# Motor-Connector.net
KiCad netlist of a schematic drawn in Altium Designer
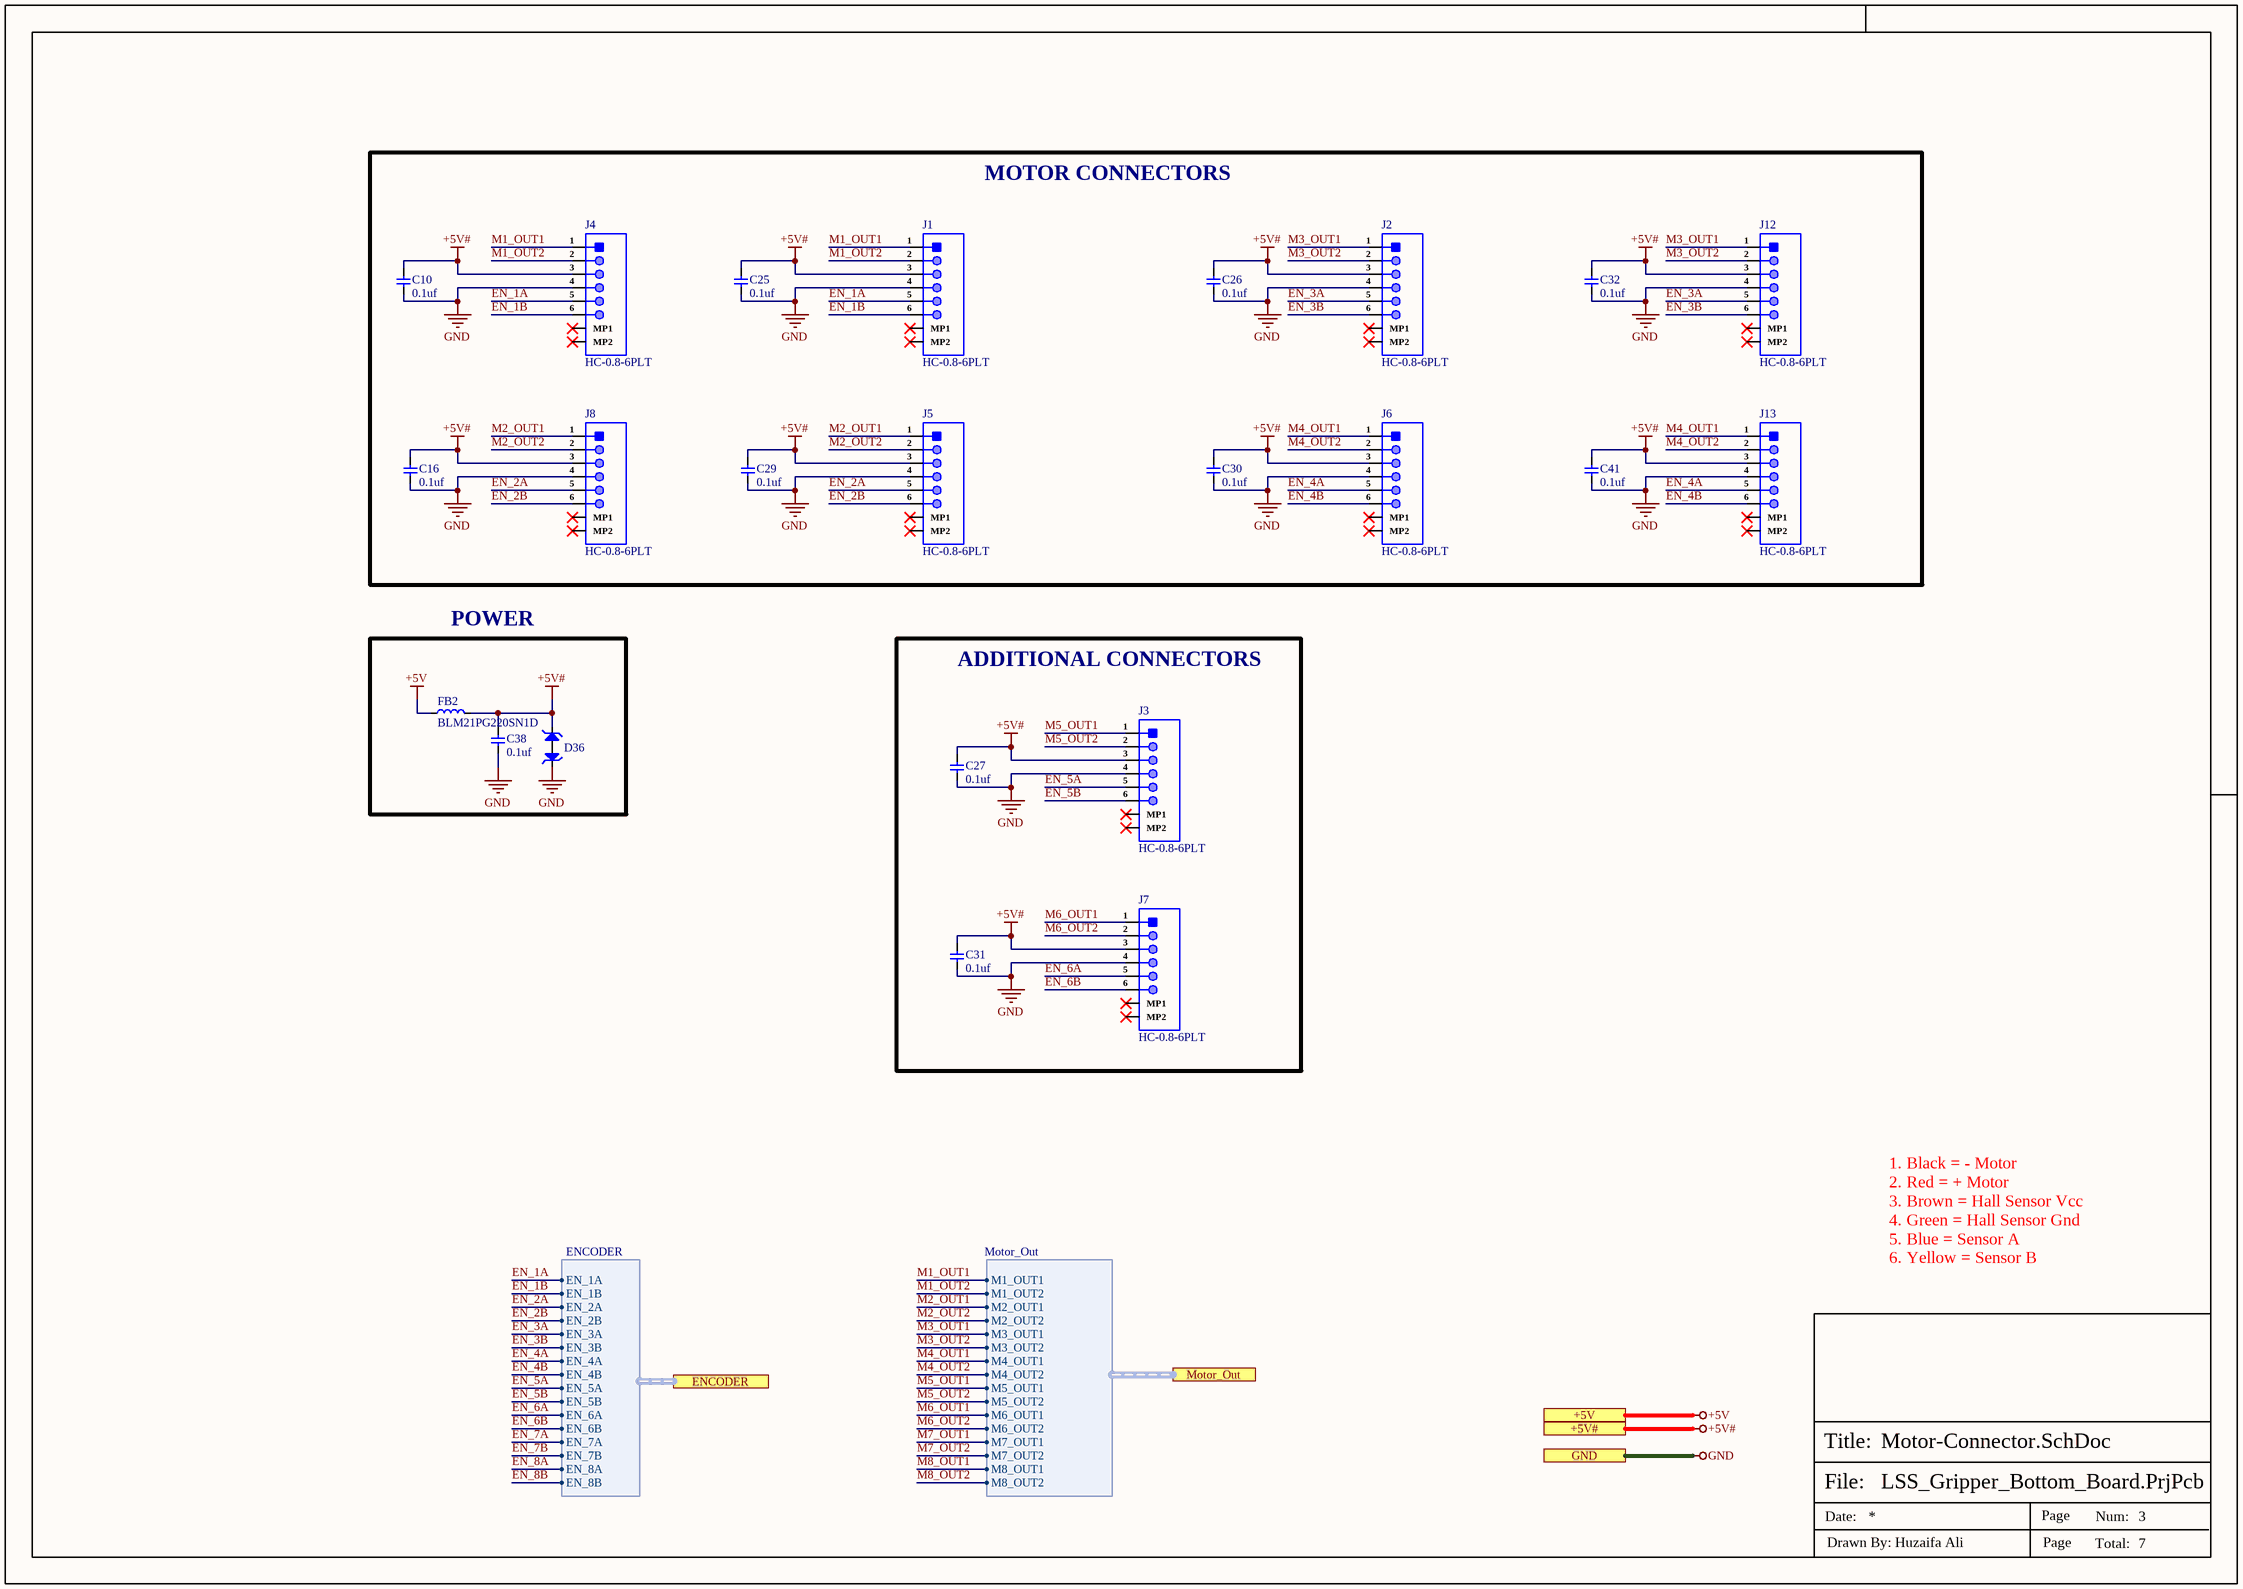
[diagram p0: Motor-Connector.SchDoc]

(export (version "E")
  (design (tool "Eeschema 10.0.6"))
  (components
    (comp (ref "C10")
      (value "0.1uf")
      (footprint "Cap-0402")
      (description "CAP CER 0.1UF 100V X5R 0402")
      (fields
        (field (name "MANUFACTURER") "Murata")
        (field (name "MANUFACTURER PART NUMBER") "GRM155R62A104KE14D")
      )
      (libsource (lib "eSpark Libraries") (part "GRM155R62A104KE14D"))
    )
    (comp (ref "C16")
      (value "0.1uf")
      (footprint "Cap-0402")
      (description "CAP CER 0.1UF 100V X5R 0402")
      (fields
        (field (name "MANUFACTURER") "Murata")
        (field (name "MANUFACTURER PART NUMBER") "GRM155R62A104KE14D")
      )
      (libsource (lib "eSpark Libraries") (part "GRM155R62A104KE14D"))
    )
    (comp (ref "C25")
      (value "0.1uf")
      (footprint "Cap-0402")
      (description "CAP CER 0.1UF 100V X5R 0402")
      (fields
        (field (name "MANUFACTURER") "Murata")
        (field (name "MANUFACTURER PART NUMBER") "GRM155R62A104KE14D")
      )
      (libsource (lib "eSpark Libraries") (part "GRM155R62A104KE14D"))
    )
    (comp (ref "C26")
      (value "0.1uf")
      (footprint "Cap-0402")
      (description "CAP CER 0.1UF 100V X5R 0402")
      (fields
        (field (name "MANUFACTURER") "Murata")
        (field (name "MANUFACTURER PART NUMBER") "GRM155R62A104KE14D")
      )
      (libsource (lib "eSpark Libraries") (part "GRM155R62A104KE14D"))
    )
    (comp (ref "C27")
      (value "0.1uf")
      (footprint "Cap-0402")
      (description "CAP CER 0.1UF 100V X5R 0402")
      (fields
        (field (name "MANUFACTURER") "Murata")
        (field (name "MANUFACTURER PART NUMBER") "GRM155R62A104KE14D")
      )
      (libsource (lib "eSpark Libraries") (part "GRM155R62A104KE14D"))
    )
    (comp (ref "C29")
      (value "0.1uf")
      (footprint "Cap-0402")
      (description "CAP CER 0.1UF 100V X5R 0402")
      (fields
        (field (name "MANUFACTURER") "Murata")
        (field (name "MANUFACTURER PART NUMBER") "GRM155R62A104KE14D")
      )
      (libsource (lib "eSpark Libraries") (part "GRM155R62A104KE14D"))
    )
    (comp (ref "C30")
      (value "0.1uf")
      (footprint "Cap-0402")
      (description "CAP CER 0.1UF 100V X5R 0402")
      (fields
        (field (name "MANUFACTURER") "Murata")
        (field (name "MANUFACTURER PART NUMBER") "GRM155R62A104KE14D")
      )
      (libsource (lib "eSpark Libraries") (part "GRM155R62A104KE14D"))
    )
    (comp (ref "C31")
      (value "0.1uf")
      (footprint "Cap-0402")
      (description "CAP CER 0.1UF 100V X5R 0402")
      (fields
        (field (name "MANUFACTURER") "Murata")
        (field (name "MANUFACTURER PART NUMBER") "GRM155R62A104KE14D")
      )
      (libsource (lib "eSpark Libraries") (part "GRM155R62A104KE14D"))
    )
    (comp (ref "C32")
      (value "0.1uf")
      (footprint "Cap-0402")
      (description "CAP CER 0.1UF 100V X5R 0402")
      (fields
        (field (name "MANUFACTURER") "Murata")
        (field (name "MANUFACTURER PART NUMBER") "GRM155R62A104KE14D")
      )
      (libsource (lib "eSpark Libraries") (part "GRM155R62A104KE14D"))
    )
    (comp (ref "C38")
      (value "0.1uf")
      (footprint "Cap-0402")
      (description "CAP CER 0.1UF 100V X5R 0402")
      (fields
        (field (name "MANUFACTURER") "Murata")
        (field (name "MANUFACTURER PART NUMBER") "GRM155R62A104KE14D")
      )
      (libsource (lib "eSpark Libraries") (part "GRM155R62A104KE14D"))
    )
    (comp (ref "C41")
      (value "0.1uf")
      (footprint "Cap-0402")
      (description "CAP CER 0.1UF 100V X5R 0402")
      (fields
        (field (name "MANUFACTURER") "Murata")
        (field (name "MANUFACTURER PART NUMBER") "GRM155R62A104KE14D")
      )
      (libsource (lib "eSpark Libraries") (part "GRM155R62A104KE14D"))
    )
    (comp (ref "D36")
      (value "PESD5V0H1BSFYL")
      (footprint "DSN0603-2")
      (description "TVS DIODE 5VWM 6.3VC DSN0603-2")
      (fields (field (name "MANUFACTURER") "Nexperia") (field (name "LCSC PART NUMBER") "C477989"))
      (libsource (lib "eSpark Libraries") (part "PESD5V0H1BSFYL"))
    )
    (comp (ref "FB2")
      (value "BLM21PG220SN1D")
      (footprint "Ind-0805")
      (description "FERRITE BEAD 22 OHM 0805 1LN")
      (fields (field (name "MANUFACTURER") "Murata") (field (name "LCSC PART NUMBER") "C88993"))
      (libsource (lib "eSpark Libraries") (part "BLM21PG220SN1D"))
    )
    (comp (ref "J1")
      (value "HC-0.8-6PLT")
      (footprint "HC-0.8-6PLT")
      (fields (field (name "MANUFACTURER") "HCTL") (field (name "LCSC PART NUMBER") "C2845356"))
      (libsource (lib "eSpark Libraries") (part "HC-0.8-6PLT"))
    )
    (comp (ref "J2")
      (value "HC-0.8-6PLT")
      (footprint "HC-0.8-6PLT")
      (fields (field (name "MANUFACTURER") "HCTL") (field (name "LCSC PART NUMBER") "C2845356"))
      (libsource (lib "eSpark Libraries") (part "HC-0.8-6PLT"))
    )
    (comp (ref "J3")
      (value "HC-0.8-6PLT")
      (footprint "HC-0.8-6PLT")
      (fields (field (name "MANUFACTURER") "HCTL") (field (name "LCSC PART NUMBER") "C2845356"))
      (libsource (lib "eSpark Libraries") (part "HC-0.8-6PLT"))
    )
    (comp (ref "J4")
      (value "HC-0.8-6PLT")
      (footprint "HC-0.8-6PLT")
      (fields (field (name "MANUFACTURER") "HCTL") (field (name "LCSC PART NUMBER") "C2845356"))
      (libsource (lib "eSpark Libraries") (part "HC-0.8-6PLT"))
    )
    (comp (ref "J5")
      (value "HC-0.8-6PLT")
      (footprint "HC-0.8-6PLT")
      (fields (field (name "MANUFACTURER") "HCTL") (field (name "LCSC PART NUMBER") "C2845356"))
      (libsource (lib "eSpark Libraries") (part "HC-0.8-6PLT"))
    )
    (comp (ref "J6")
      (value "HC-0.8-6PLT")
      (footprint "HC-0.8-6PLT")
      (fields (field (name "MANUFACTURER") "HCTL") (field (name "LCSC PART NUMBER") "C2845356"))
      (libsource (lib "eSpark Libraries") (part "HC-0.8-6PLT"))
    )
    (comp (ref "J7")
      (value "HC-0.8-6PLT")
      (footprint "HC-0.8-6PLT")
      (fields (field (name "MANUFACTURER") "HCTL") (field (name "LCSC PART NUMBER") "C2845356"))
      (libsource (lib "eSpark Libraries") (part "HC-0.8-6PLT"))
    )
    (comp (ref "J8")
      (value "HC-0.8-6PLT")
      (footprint "HC-0.8-6PLT")
      (fields (field (name "MANUFACTURER") "HCTL") (field (name "LCSC PART NUMBER") "C2845356"))
      (libsource (lib "eSpark Libraries") (part "HC-0.8-6PLT"))
    )
    (comp (ref "J12")
      (value "HC-0.8-6PLT")
      (footprint "HC-0.8-6PLT")
      (fields (field (name "MANUFACTURER") "HCTL") (field (name "LCSC PART NUMBER") "C2845356"))
      (libsource (lib "eSpark Libraries") (part "HC-0.8-6PLT"))
    )
    (comp (ref "J13")
      (value "HC-0.8-6PLT")
      (footprint "HC-0.8-6PLT")
      (fields (field (name "MANUFACTURER") "HCTL") (field (name "LCSC PART NUMBER") "C2845356"))
      (libsource (lib "eSpark Libraries") (part "HC-0.8-6PLT"))
    )
  )
  (nets
    (net (code "3") (name "+5V") (class "Default")
      (node (ref "FB2") (pin "1") (pinfunction "1_1") (pintype "passive"))
    )
    (net (code "4") (name "+5V#") (class "Default")
      (node (ref "C10") (pin "2") (pinfunction "2_2") (pintype "passive"))
      (node (ref "C16") (pin "2") (pinfunction "2_2") (pintype "passive"))
      (node (ref "C25") (pin "2") (pinfunction "2_2") (pintype "passive"))
      (node (ref "C26") (pin "2") (pinfunction "2_2") (pintype "passive"))
      (node (ref "C27") (pin "2") (pinfunction "2_2") (pintype "passive"))
      (node (ref "C29") (pin "2") (pinfunction "2_2") (pintype "passive"))
      (node (ref "C30") (pin "2") (pinfunction "2_2") (pintype "passive"))
      (node (ref "C31") (pin "2") (pinfunction "2_2") (pintype "passive"))
      (node (ref "C32") (pin "2") (pinfunction "2_2") (pintype "passive"))
      (node (ref "C38") (pin "2") (pinfunction "2_2") (pintype "passive"))
      (node (ref "C41") (pin "2") (pinfunction "2_2") (pintype "passive"))
      (node (ref "D36") (pin "1") (pinfunction "1_1") (pintype "passive"))
      (node (ref "FB2") (pin "2") (pinfunction "2_2") (pintype "passive"))
      (node (ref "J1") (pin "3") (pinfunction "3_3") (pintype "passive"))
      (node (ref "J12") (pin "3") (pinfunction "3_3") (pintype "passive"))
      (node (ref "J13") (pin "3") (pinfunction "3_3") (pintype "passive"))
      (node (ref "J2") (pin "3") (pinfunction "3_3") (pintype "passive"))
      (node (ref "J3") (pin "3") (pinfunction "3_3") (pintype "passive"))
      (node (ref "J4") (pin "3") (pinfunction "3_3") (pintype "passive"))
      (node (ref "J5") (pin "3") (pinfunction "3_3") (pintype "passive"))
      (node (ref "J6") (pin "3") (pinfunction "3_3") (pintype "passive"))
      (node (ref "J7") (pin "3") (pinfunction "3_3") (pintype "passive"))
      (node (ref "J8") (pin "3") (pinfunction "3_3") (pintype "passive"))
    )
    (net (code "5") (name "/EN_1A") (class "Default")
      (node (ref "J1") (pin "5") (pinfunction "5_5") (pintype "passive"))
      (node (ref "J4") (pin "5") (pinfunction "5_5") (pintype "passive"))
    )
    (net (code "6") (name "/EN_1B") (class "Default")
      (node (ref "J1") (pin "6") (pinfunction "6_6") (pintype "passive"))
      (node (ref "J4") (pin "6") (pinfunction "6_6") (pintype "passive"))
    )
    (net (code "7") (name "/EN_2A") (class "Default")
      (node (ref "J5") (pin "5") (pinfunction "5_5") (pintype "passive"))
      (node (ref "J8") (pin "5") (pinfunction "5_5") (pintype "passive"))
    )
    (net (code "8") (name "/EN_2B") (class "Default")
      (node (ref "J5") (pin "6") (pinfunction "6_6") (pintype "passive"))
      (node (ref "J8") (pin "6") (pinfunction "6_6") (pintype "passive"))
    )
    (net (code "9") (name "/EN_3A") (class "Default")
      (node (ref "J12") (pin "5") (pinfunction "5_5") (pintype "passive"))
      (node (ref "J2") (pin "5") (pinfunction "5_5") (pintype "passive"))
    )
    (net (code "10") (name "/EN_3B") (class "Default")
      (node (ref "J12") (pin "6") (pinfunction "6_6") (pintype "passive"))
      (node (ref "J2") (pin "6") (pinfunction "6_6") (pintype "passive"))
    )
    (net (code "11") (name "/EN_4A") (class "Default")
      (node (ref "J13") (pin "5") (pinfunction "5_5") (pintype "passive"))
      (node (ref "J6") (pin "5") (pinfunction "5_5") (pintype "passive"))
    )
    (net (code "12") (name "/EN_4B") (class "Default")
      (node (ref "J13") (pin "6") (pinfunction "6_6") (pintype "passive"))
      (node (ref "J6") (pin "6") (pinfunction "6_6") (pintype "passive"))
    )
    (net (code "13") (name "/EN_5A") (class "Default")
      (node (ref "J3") (pin "5") (pinfunction "5_5") (pintype "passive"))
    )
    (net (code "14") (name "/EN_5B") (class "Default")
      (node (ref "J3") (pin "6") (pinfunction "6_6") (pintype "passive"))
    )
    (net (code "15") (name "/EN_6A") (class "Default")
      (node (ref "J7") (pin "5") (pinfunction "5_5") (pintype "passive"))
    )
    (net (code "16") (name "/EN_6B") (class "Default")
      (node (ref "J7") (pin "6") (pinfunction "6_6") (pintype "passive"))
    )
    (net (code "21") (name "/M1_OUT1") (class "Default")
      (node (ref "J1") (pin "1") (pinfunction "1_1") (pintype "passive"))
      (node (ref "J4") (pin "1") (pinfunction "1_1") (pintype "passive"))
    )
    (net (code "22") (name "/M1_OUT2") (class "Default")
      (node (ref "J1") (pin "2") (pinfunction "2_2") (pintype "passive"))
      (node (ref "J4") (pin "2") (pinfunction "2_2") (pintype "passive"))
    )
    (net (code "23") (name "/M2_OUT1") (class "Default")
      (node (ref "J5") (pin "1") (pinfunction "1_1") (pintype "passive"))
      (node (ref "J8") (pin "1") (pinfunction "1_1") (pintype "passive"))
    )
    (net (code "24") (name "/M2_OUT2") (class "Default")
      (node (ref "J5") (pin "2") (pinfunction "2_2") (pintype "passive"))
      (node (ref "J8") (pin "2") (pinfunction "2_2") (pintype "passive"))
    )
    (net (code "25") (name "/M3_OUT1") (class "Default")
      (node (ref "J12") (pin "1") (pinfunction "1_1") (pintype "passive"))
      (node (ref "J2") (pin "1") (pinfunction "1_1") (pintype "passive"))
    )
    (net (code "26") (name "/M3_OUT2") (class "Default")
      (node (ref "J12") (pin "2") (pinfunction "2_2") (pintype "passive"))
      (node (ref "J2") (pin "2") (pinfunction "2_2") (pintype "passive"))
    )
    (net (code "27") (name "/M4_OUT1") (class "Default")
      (node (ref "J13") (pin "1") (pinfunction "1_1") (pintype "passive"))
      (node (ref "J6") (pin "1") (pinfunction "1_1") (pintype "passive"))
    )
    (net (code "28") (name "/M4_OUT2") (class "Default")
      (node (ref "J13") (pin "2") (pinfunction "2_2") (pintype "passive"))
      (node (ref "J6") (pin "2") (pinfunction "2_2") (pintype "passive"))
    )
    (net (code "29") (name "/M5_OUT1") (class "Default")
      (node (ref "J3") (pin "1") (pinfunction "1_1") (pintype "passive"))
    )
    (net (code "30") (name "/M5_OUT2") (class "Default")
      (node (ref "J3") (pin "2") (pinfunction "2_2") (pintype "passive"))
    )
    (net (code "31") (name "/M6_OUT1") (class "Default")
      (node (ref "J7") (pin "1") (pinfunction "1_1") (pintype "passive"))
    )
    (net (code "32") (name "/M6_OUT2") (class "Default")
      (node (ref "J7") (pin "2") (pinfunction "2_2") (pintype "passive"))
    )
    (net (code "39") (name "GND") (class "Default")
      (node (ref "C10") (pin "1") (pinfunction "1_1") (pintype "passive"))
      (node (ref "C16") (pin "1") (pinfunction "1_1") (pintype "passive"))
      (node (ref "C25") (pin "1") (pinfunction "1_1") (pintype "passive"))
      (node (ref "C26") (pin "1") (pinfunction "1_1") (pintype "passive"))
      (node (ref "C27") (pin "1") (pinfunction "1_1") (pintype "passive"))
      (node (ref "C29") (pin "1") (pinfunction "1_1") (pintype "passive"))
      (node (ref "C30") (pin "1") (pinfunction "1_1") (pintype "passive"))
      (node (ref "C31") (pin "1") (pinfunction "1_1") (pintype "passive"))
      (node (ref "C32") (pin "1") (pinfunction "1_1") (pintype "passive"))
      (node (ref "C38") (pin "1") (pinfunction "1_1") (pintype "passive"))
      (node (ref "C41") (pin "1") (pinfunction "1_1") (pintype "passive"))
      (node (ref "D36") (pin "2") (pinfunction "2_2") (pintype "passive"))
      (node (ref "J1") (pin "4") (pinfunction "4_4") (pintype "passive"))
      (node (ref "J12") (pin "4") (pinfunction "4_4") (pintype "passive"))
      (node (ref "J13") (pin "4") (pinfunction "4_4") (pintype "passive"))
      (node (ref "J2") (pin "4") (pinfunction "4_4") (pintype "passive"))
      (node (ref "J3") (pin "4") (pinfunction "4_4") (pintype "passive"))
      (node (ref "J4") (pin "4") (pinfunction "4_4") (pintype "passive"))
      (node (ref "J5") (pin "4") (pinfunction "4_4") (pintype "passive"))
      (node (ref "J6") (pin "4") (pinfunction "4_4") (pintype "passive"))
      (node (ref "J7") (pin "4") (pinfunction "4_4") (pintype "passive"))
      (node (ref "J8") (pin "4") (pinfunction "4_4") (pintype "passive"))
    )
    (net (code "40") (name "unconnected-(J1-PadMP1)") (class "Default")
      (node (ref "J1") (pin "MP1") (pinfunction "MP1_MP1") (pintype "passive+no_connect"))
    )
    (net (code "41") (name "unconnected-(J1-PadMP2)") (class "Default")
      (node (ref "J1") (pin "MP2") (pinfunction "MP2_MP2") (pintype "passive+no_connect"))
    )
    (net (code "42") (name "unconnected-(J2-PadMP1)") (class "Default")
      (node (ref "J2") (pin "MP1") (pinfunction "MP1_MP1") (pintype "passive+no_connect"))
    )
    (net (code "43") (name "unconnected-(J2-PadMP2)") (class "Default")
      (node (ref "J2") (pin "MP2") (pinfunction "MP2_MP2") (pintype "passive+no_connect"))
    )
    (net (code "44") (name "unconnected-(J3-PadMP1)") (class "Default")
      (node (ref "J3") (pin "MP1") (pinfunction "MP1_MP1") (pintype "passive+no_connect"))
    )
    (net (code "45") (name "unconnected-(J3-PadMP2)") (class "Default")
      (node (ref "J3") (pin "MP2") (pinfunction "MP2_MP2") (pintype "passive+no_connect"))
    )
    (net (code "46") (name "unconnected-(J4-PadMP1)") (class "Default")
      (node (ref "J4") (pin "MP1") (pinfunction "MP1_MP1") (pintype "passive+no_connect"))
    )
    (net (code "47") (name "unconnected-(J4-PadMP2)") (class "Default")
      (node (ref "J4") (pin "MP2") (pinfunction "MP2_MP2") (pintype "passive+no_connect"))
    )
    (net (code "48") (name "unconnected-(J5-PadMP1)") (class "Default")
      (node (ref "J5") (pin "MP1") (pinfunction "MP1_MP1") (pintype "passive+no_connect"))
    )
    (net (code "49") (name "unconnected-(J5-PadMP2)") (class "Default")
      (node (ref "J5") (pin "MP2") (pinfunction "MP2_MP2") (pintype "passive+no_connect"))
    )
    (net (code "50") (name "unconnected-(J6-PadMP1)") (class "Default")
      (node (ref "J6") (pin "MP1") (pinfunction "MP1_MP1") (pintype "passive+no_connect"))
    )
    (net (code "51") (name "unconnected-(J6-PadMP2)") (class "Default")
      (node (ref "J6") (pin "MP2") (pinfunction "MP2_MP2") (pintype "passive+no_connect"))
    )
    (net (code "52") (name "unconnected-(J7-PadMP1)") (class "Default")
      (node (ref "J7") (pin "MP1") (pinfunction "MP1_MP1") (pintype "passive+no_connect"))
    )
    (net (code "53") (name "unconnected-(J7-PadMP2)") (class "Default")
      (node (ref "J7") (pin "MP2") (pinfunction "MP2_MP2") (pintype "passive+no_connect"))
    )
    (net (code "54") (name "unconnected-(J8-PadMP1)") (class "Default")
      (node (ref "J8") (pin "MP1") (pinfunction "MP1_MP1") (pintype "passive+no_connect"))
    )
    (net (code "55") (name "unconnected-(J8-PadMP2)") (class "Default")
      (node (ref "J8") (pin "MP2") (pinfunction "MP2_MP2") (pintype "passive+no_connect"))
    )
    (net (code "56") (name "unconnected-(J12-PadMP1)") (class "Default")
      (node (ref "J12") (pin "MP1") (pinfunction "MP1_MP1") (pintype "passive+no_connect"))
    )
    (net (code "57") (name "unconnected-(J12-PadMP2)") (class "Default")
      (node (ref "J12") (pin "MP2") (pinfunction "MP2_MP2") (pintype "passive+no_connect"))
    )
    (net (code "58") (name "unconnected-(J13-PadMP1)") (class "Default")
      (node (ref "J13") (pin "MP1") (pinfunction "MP1_MP1") (pintype "passive+no_connect"))
    )
    (net (code "59") (name "unconnected-(J13-PadMP2)") (class "Default")
      (node (ref "J13") (pin "MP2") (pinfunction "MP2_MP2") (pintype "passive+no_connect"))
    )
  )
)
